# pca10059.net
KiCad netlist of a schematic drawn in Altium Designer
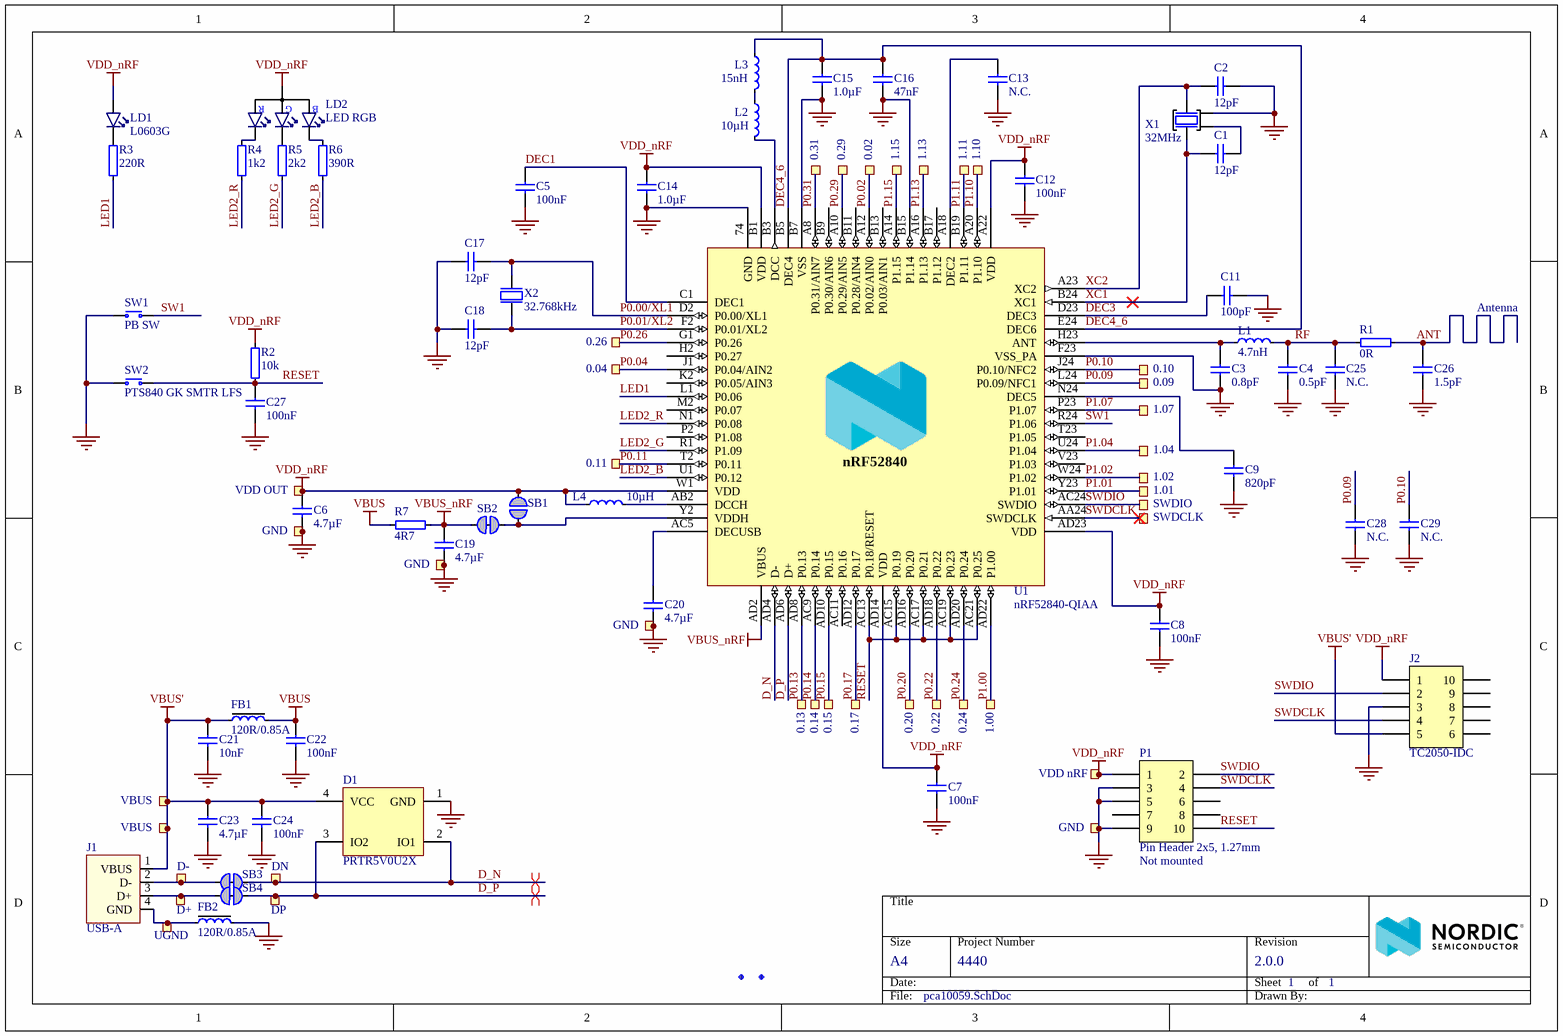
[diagram p0: pca10059.SchDoc]

(export (version "E")
  (design (tool "Eeschema 10.0.6"))
  (components
    (comp (ref "0.02")
      (value "CH")
      (footprint "Castellated_Hole_0.9mm")
      (description "Castellated Hole 0.9mm")
      (fields (field (name "PUBLISHER") "Nordic Semiconductor"))
      (libsource (lib "") (part "TESTPAD_1"))
    )
    (comp (ref "0.04")
      (value "Ø1.0mm,SMD")
      (footprint "TP_SMD_Ø1.0mm")
      (description "1.0mm circular SMD testpad")
      (fields
        (field (name "PART NUMBER") "TP_SMD_Ø1.0MM")
        (field (name "MANUFACTURER") "Nordic Semiconductor")
        (field (name "PUBLISHER") "Nordic Semiconductor")
      )
      (libsource (lib "Nordic Passive DB") (part "TESTPAD"))
    )
    (comp (ref "0.09")
      (value "CH")
      (footprint "Castellated_Hole_0.9mm")
      (description "Castellated Hole 0.9mm")
      (fields (field (name "PUBLISHER") "Nordic Semiconductor"))
      (libsource (lib "") (part "TESTPAD_3"))
    )
    (comp (ref "0.10")
      (value "CH")
      (footprint "Castellated_Hole_0.9mm")
      (description "Castellated Hole 0.9mm")
      (fields (field (name "PUBLISHER") "Nordic Semiconductor"))
      (libsource (lib "") (part "TESTPAD_3"))
    )
    (comp (ref "0.11")
      (value "Ø1.0mm,SMD")
      (footprint "TP_SMD_Ø1.0mm")
      (description "1.0mm circular SMD testpad")
      (fields
        (field (name "PART NUMBER") "TP_SMD_Ø1.0MM")
        (field (name "MANUFACTURER") "Nordic Semiconductor")
        (field (name "PUBLISHER") "Nordic Semiconductor")
      )
      (libsource (lib "Nordic Passive DB") (part "TESTPAD"))
    )
    (comp (ref "0.13")
      (value "CH")
      (footprint "Castellated_Hole_0.9mm")
      (description "Castellated Hole 0.9mm")
      (fields (field (name "PUBLISHER") "Nordic Semiconductor"))
      (libsource (lib "") (part "TESTPAD_2"))
    )
    (comp (ref "0.14")
      (value "Ø1.0mm,SMD")
      (footprint "TP_SMD_Ø1.0mm")
      (description "1.0mm circular SMD testpad")
      (fields
        (field (name "PART NUMBER") "TP_SMD_Ø1.0MM")
        (field (name "MANUFACTURER") "Nordic Semiconductor")
        (field (name "PUBLISHER") "Nordic Semiconductor")
      )
      (libsource (lib "") (part "TESTPAD_2"))
    )
    (comp (ref "0.15")
      (value "CH")
      (footprint "Castellated_Hole_0.9mm")
      (description "Castellated Hole 0.9mm")
      (fields (field (name "PUBLISHER") "Nordic Semiconductor"))
      (libsource (lib "") (part "TESTPAD_2"))
    )
    (comp (ref "0.17")
      (value "CH")
      (footprint "Castellated_Hole_0.9mm")
      (description "Castellated Hole 0.9mm")
      (fields (field (name "PUBLISHER") "Nordic Semiconductor"))
      (libsource (lib "") (part "TESTPAD_2"))
    )
    (comp (ref "0.20")
      (value "CH")
      (footprint "Castellated_Hole_0.9mm")
      (description "Castellated Hole 0.9mm")
      (fields (field (name "PUBLISHER") "Nordic Semiconductor"))
      (libsource (lib "") (part "TESTPAD_2"))
    )
    (comp (ref "0.22")
      (value "CH")
      (footprint "Castellated_Hole_0.9mm")
      (description "Castellated Hole 0.9mm")
      (fields (field (name "PUBLISHER") "Nordic Semiconductor"))
      (libsource (lib "") (part "TESTPAD_2"))
    )
    (comp (ref "0.24")
      (value "CH")
      (footprint "Castellated_Hole_0.9mm")
      (description "Castellated Hole 0.9mm")
      (fields (field (name "PUBLISHER") "Nordic Semiconductor"))
      (libsource (lib "") (part "TESTPAD_2"))
    )
    (comp (ref "0.26")
      (value "Ø1.0mm,SMD")
      (footprint "TP_SMD_Ø1.0mm")
      (description "1.0mm circular SMD testpad")
      (fields
        (field (name "PART NUMBER") "TP_SMD_Ø1.0MM")
        (field (name "MANUFACTURER") "Nordic Semiconductor")
        (field (name "PUBLISHER") "Nordic Semiconductor")
      )
      (libsource (lib "Nordic Passive DB") (part "TESTPAD"))
    )
    (comp (ref "0.29")
      (value "CH")
      (footprint "Castellated_Hole_0.9mm")
      (description "Castellated Hole 0.9mm")
      (fields (field (name "PUBLISHER") "Nordic Semiconductor"))
      (libsource (lib "") (part "TESTPAD_1"))
    )
    (comp (ref "0.31")
      (value "CH")
      (footprint "Castellated_Hole_0.9mm")
      (description "Castellated Hole 0.9mm")
      (fields (field (name "PUBLISHER") "Nordic Semiconductor"))
      (libsource (lib "") (part "TESTPAD_1"))
    )
    (comp (ref "1.00")
      (value "CH")
      (footprint "Castellated_Hole_0.9mm")
      (description "Castellated Hole 0.9mm")
      (fields (field (name "PUBLISHER") "Nordic Semiconductor"))
      (libsource (lib "") (part "TESTPAD_2"))
    )
    (comp (ref "1.01")
      (value "Ø1.0mm,SMD")
      (footprint "TP_SMD_Ø1.0mm")
      (description "1.0mm circular SMD testpad")
      (fields
        (field (name "PART NUMBER") "TP_SMD_Ø1.0MM")
        (field (name "MANUFACTURER") "Nordic Semiconductor")
        (field (name "PUBLISHER") "Nordic Semiconductor")
      )
      (libsource (lib "") (part "TESTPAD_3"))
    )
    (comp (ref "1.02")
      (value "Ø1.0mm,SMD")
      (footprint "TP_SMD_Ø1.0mm")
      (description "1.0mm circular SMD testpad")
      (fields
        (field (name "PART NUMBER") "TP_SMD_Ø1.0MM")
        (field (name "MANUFACTURER") "Nordic Semiconductor")
        (field (name "PUBLISHER") "Nordic Semiconductor")
      )
      (libsource (lib "") (part "TESTPAD_3"))
    )
    (comp (ref "1.04")
      (value "Ø1.0mm,SMD")
      (footprint "TP_SMD_Ø1.0mm")
      (description "1.0mm circular SMD testpad")
      (fields
        (field (name "PART NUMBER") "TP_SMD_Ø1.0MM")
        (field (name "MANUFACTURER") "Nordic Semiconductor")
        (field (name "PUBLISHER") "Nordic Semiconductor")
      )
      (libsource (lib "") (part "TESTPAD_3"))
    )
    (comp (ref "1.07")
      (value "Ø1.0mm,SMD")
      (footprint "TP_SMD_Ø1.0mm")
      (description "1.0mm circular SMD testpad")
      (fields
        (field (name "PART NUMBER") "TP_SMD_Ø1.0MM")
        (field (name "MANUFACTURER") "Nordic Semiconductor")
        (field (name "PUBLISHER") "Nordic Semiconductor")
      )
      (libsource (lib "") (part "TESTPAD_3"))
    )
    (comp (ref "1.10")
      (value "CH")
      (footprint "Castellated_Hole_0.9mm")
      (description "Castellated Hole 0.9mm")
      (fields (field (name "PUBLISHER") "Nordic Semiconductor"))
      (libsource (lib "") (part "TESTPAD_1"))
    )
    (comp (ref "1.11")
      (value "Ø1.0mm,SMD")
      (footprint "TP_SMD_Ø1.0mm")
      (description "1.0mm circular SMD testpad")
      (fields
        (field (name "PART NUMBER") "TP_SMD_Ø1.0MM")
        (field (name "MANUFACTURER") "Nordic Semiconductor")
        (field (name "PUBLISHER") "Nordic Semiconductor")
      )
      (libsource (lib "") (part "TESTPAD_1"))
    )
    (comp (ref "1.13")
      (value "CH")
      (footprint "Castellated_Hole_0.9mm")
      (description "Castellated Hole 0.9mm")
      (fields (field (name "PUBLISHER") "Nordic Semiconductor"))
      (libsource (lib "") (part "TESTPAD_1"))
    )
    (comp (ref "1.15")
      (value "CH")
      (footprint "Castellated_Hole_0.9mm")
      (description "Castellated Hole 0.9mm")
      (fields (field (name "PUBLISHER") "Nordic Semiconductor"))
      (libsource (lib "") (part "TESTPAD_1"))
    )
    (comp (ref "C1")
      (value "12pF")
      (footprint "CAPC0603X03L_C")
      (description "Capacitor, NP0, ±2%")
      (fields (field (name "PART NUMBER") "C0201-12p") (field (name "PUBLISHER") "Nordic Semiconductor"))
      (libsource (lib "Nordic Passive DB") (part "CAP"))
    )
    (comp (ref "C2")
      (value "12pF")
      (footprint "CAPC0603X03L_C")
      (description "Capacitor, NP0, ±2%")
      (fields (field (name "PART NUMBER") "C0201-12p") (field (name "PUBLISHER") "Nordic Semiconductor"))
      (libsource (lib "Nordic Passive DB") (part "CAP"))
    )
    (comp (ref "C3")
      (value "0.8pF")
      (footprint "CAPC0603X03L_C")
      (description "Capacitor, NP0, ±0.05pF, 50V")
      (fields
        (field (name "PART NUMBER") "C0201-0.8p")
        (field (name "MANUFACTURER") "Murata")
        (field (name "PUBLISHER") "Nordic Semiconductor")
      )
      (libsource (lib "Nordic Passive DB") (part "CAP"))
    )
    (comp (ref "C4")
      (value "0.5pF")
      (footprint "CAPC0603X03L_C")
      (description "Capacitor, NP0, ±0.05pF")
      (fields (field (name "PART NUMBER") "C0201-0.5p") (field (name "PUBLISHER") "Nordic Semiconductor"))
      (libsource (lib "Nordic Passive DB") (part "CAP"))
    )
    (comp (ref "C5")
      (value "100nF")
      (footprint "CAPC0603X03L_C")
      (description "Capacitor, X5R, ±10%")
      (fields (field (name "PART NUMBER") "C0201-100n") (field (name "PUBLISHER") "Nordic Semiconductor"))
      (libsource (lib "Nordic Passive DB") (part "CAP"))
    )
    (comp (ref "C6")
      (value "4.7µF")
      (footprint "CAPC1608X06L")
      (description "Capacitor, X5R, ±10%")
      (fields (field (name "PART NUMBER") "C0603-4µ7") (field (name "PUBLISHER") "Nordic Semiconductor"))
      (libsource (lib "Nordic Passive DB") (part "CAP"))
    )
    (comp (ref "C7")
      (value "100nF")
      (footprint "CAPC0603X03L_C")
      (description "Capacitor, X5R, ±10%")
      (fields (field (name "PART NUMBER") "C0201-100n") (field (name "PUBLISHER") "Nordic Semiconductor"))
      (libsource (lib "Nordic Passive DB") (part "CAP"))
    )
    (comp (ref "C8")
      (value "100nF")
      (footprint "CAPC0603X03L_C")
      (description "Capacitor, X5R, ±10%")
      (fields (field (name "PART NUMBER") "C0201-100n") (field (name "PUBLISHER") "Nordic Semiconductor"))
      (libsource (lib "Nordic Passive DB") (part "CAP"))
    )
    (comp (ref "C9")
      (value "820pF")
      (footprint "CAPC0603X03L_C")
      (description "Capacitor, X7R, ±10%")
      (fields (field (name "PART NUMBER") "C0201-820p") (field (name "PUBLISHER") "Nordic Semiconductor"))
      (libsource (lib "Nordic Passive DB") (part "CAP"))
    )
    (comp (ref "C11")
      (value "100pF")
      (footprint "CAPC0603X03L_C")
      (description "Capacitor, NP0, ±2%, 25V")
      (fields
        (field (name "PART NUMBER") "C0201-100p")
        (field (name "MANUFACTURER") "Murata")
        (field (name "PUBLISHER") "Nordic Semiconductor")
      )
      (libsource (lib "Nordic Passive DB") (part "CAP"))
    )
    (comp (ref "C12")
      (value "100nF")
      (footprint "CAPC0603X03L_C")
      (description "Capacitor, X5R, ±10%")
      (fields (field (name "PART NUMBER") "C0201-100n") (field (name "PUBLISHER") "Nordic Semiconductor"))
      (libsource (lib "Nordic Passive DB") (part "CAP"))
    )
    (comp (ref "C13")
      (value "N.C.")
      (footprint "CAPC0603X03L_C")
      (description "Not mounted")
      (fields (field (name "PART NUMBER") "C0201-N.C.") (field (name "PUBLISHER") "Nordic Semiconductor"))
      (libsource (lib "Nordic Passive DB") (part "CAP"))
    )
    (comp (ref "C14")
      (value "1.0µF")
      (footprint "CAPC1608X06L")
      (description "Capacitor, X7R, ±10%")
      (fields (field (name "PART NUMBER") "C0603-1µ0") (field (name "PUBLISHER") "Nordic Semiconductor"))
      (libsource (lib "Nordic Passive DB") (part "CAP"))
    )
    (comp (ref "C15")
      (value "1.0µF")
      (footprint "CAPC1608X06L")
      (description "Capacitor, X7R, ±10%")
      (fields (field (name "PART NUMBER") "C0603-1µ0") (field (name "PUBLISHER") "Nordic Semiconductor"))
      (libsource (lib "Nordic Passive DB") (part "CAP"))
    )
    (comp (ref "C16")
      (value "47nF")
      (footprint "CAPC0603X03L_C")
      (description "Capacitor, X5R, ±10%")
      (fields (field (name "PART NUMBER") "C0201-47n") (field (name "PUBLISHER") "Nordic Semiconductor"))
      (libsource (lib "Nordic Passive DB") (part "CAP"))
    )
    (comp (ref "C17")
      (value "12pF")
      (footprint "CAPC0603X03L_C")
      (description "Capacitor, NP0, ±2%")
      (fields (field (name "PART NUMBER") "C0201-12p") (field (name "PUBLISHER") "Nordic Semiconductor"))
      (libsource (lib "Nordic Passive DB") (part "CAP"))
    )
    (comp (ref "C18")
      (value "12pF")
      (footprint "CAPC0603X03L_C")
      (description "Capacitor, NP0, ±2%")
      (fields (field (name "PART NUMBER") "C0201-12p") (field (name "PUBLISHER") "Nordic Semiconductor"))
      (libsource (lib "Nordic Passive DB") (part "CAP"))
    )
    (comp (ref "C19")
      (value "4.7µF")
      (footprint "CAPC1005X04L")
      (description "Capacitor, X5R, ±20%")
      (fields (field (name "PART NUMBER") "C0402-4µ7") (field (name "PUBLISHER") "Nordic Semiconductor"))
      (libsource (lib "Nordic Passive DB") (part "CAP"))
    )
    (comp (ref "C20")
      (value "4.7µF")
      (footprint "CAPC1608X06L")
      (description "Capacitor, X5R, ±10%")
      (fields (field (name "PART NUMBER") "C0603-4µ7") (field (name "PUBLISHER") "Nordic Semiconductor"))
      (libsource (lib "Nordic Passive DB") (part "CAP"))
    )
    (comp (ref "C21")
      (value "10nF")
      (footprint "CAPC0603X03L_C")
      (description "Capacitor, X7R, ±10%")
      (fields (field (name "PART NUMBER") "C0201-10n") (field (name "PUBLISHER") "Nordic Semiconductor"))
      (libsource (lib "Nordic Passive DB") (part "CAP"))
    )
    (comp (ref "C22")
      (value "100nF")
      (footprint "CAPC0603X03L_C")
      (description "Capacitor, X5R, ±10%")
      (fields (field (name "PART NUMBER") "C0201-100n") (field (name "PUBLISHER") "Nordic Semiconductor"))
      (libsource (lib "Nordic Passive DB") (part "CAP"))
    )
    (comp (ref "C23")
      (value "4.7µF")
      (footprint "CAPC1005X04L")
      (description "Capacitor, X5R, ±20%")
      (fields (field (name "PART NUMBER") "C0402-4µ7") (field (name "PUBLISHER") "Nordic Semiconductor"))
      (libsource (lib "Nordic Passive DB") (part "CAP"))
    )
    (comp (ref "C24")
      (value "100nF")
      (footprint "CAPC0603X03L_C")
      (description "Capacitor, X5R, ±10%")
      (fields (field (name "PART NUMBER") "C0201-100n") (field (name "PUBLISHER") "Nordic Semiconductor"))
      (libsource (lib "Nordic Passive DB") (part "CAP"))
    )
    (comp (ref "C25")
      (value "N.C.")
      (footprint "CAPC0603X03L_C")
      (description "Not mounted")
      (fields (field (name "PART NUMBER") "C0201-N.C.") (field (name "PUBLISHER") "Nordic Semiconductor"))
      (libsource (lib "Nordic Passive DB") (part "CAP"))
    )
    (comp (ref "C26")
      (value "1.5pF")
      (footprint "CAPC0603X03L_C")
      (description "Capacitor, NP0, ±0.1pF")
      (fields (field (name "PART NUMBER") "C0201-1.5p") (field (name "PUBLISHER") "Nordic Semiconductor"))
      (libsource (lib "Nordic Passive DB") (part "CAP"))
    )
    (comp (ref "C27")
      (value "100nF")
      (footprint "CAPC0603X03L_C")
      (description "Capacitor, X5R, ±10%")
      (fields (field (name "PART NUMBER") "C0201-100n") (field (name "PUBLISHER") "Nordic Semiconductor"))
      (libsource (lib "Nordic Passive DB") (part "CAP"))
    )
    (comp (ref "C28")
      (value "N.C.")
      (footprint "CAPC1005X04L")
      (description "Not mounted")
      (fields (field (name "PART NUMBER") "C0402-N.C.") (field (name "PUBLISHER") "Nordic Semiconductor"))
      (libsource (lib "Nordic Passive DB") (part "CAP"))
    )
    (comp (ref "C29")
      (value "N.C.")
      (footprint "CAPC1005X04L")
      (description "Not mounted")
      (fields (field (name "PART NUMBER") "C0402-N.C.") (field (name "PUBLISHER") "Nordic Semiconductor"))
      (libsource (lib "Nordic Passive DB") (part "CAP"))
    )
    (comp (ref "D+")
      (value "Ø1.0mm,SMD")
      (footprint "TP_SMD_Ø1.0mm")
      (description "1.0mm circular SMD testpad")
      (fields
        (field (name "PART NUMBER") "TP_SMD_Ø1.0MM")
        (field (name "MANUFACTURER") "Nordic Semiconductor")
        (field (name "PUBLISHER") "Nordic Semiconductor")
      )
      (libsource (lib "") (part "TESTPAD_2"))
    )
    (comp (ref "D-")
      (value "Ø1.0mm,SMD")
      (footprint "TP_SMD_Ø1.0mm")
      (description "1.0mm circular SMD testpad")
      (fields
        (field (name "PART NUMBER") "TP_SMD_Ø1.0MM")
        (field (name "MANUFACTURER") "Nordic Semiconductor")
        (field (name "PUBLISHER") "Nordic Semiconductor")
      )
      (libsource (lib "") (part "TESTPAD_1"))
    )
    (comp (ref "D1")
      (value "PRTR5V0U2X")
      (footprint "SOT190P230X110-4L")
      (description "Ultra low capacitance double rail-to-rail ESD protection diode")
      (fields (field (name "MANUFACTURER") "NXP") (field (name "PUBLISHER") "Nordic Semiconductor"))
      (libsource (lib "Nordic Discrete DB") (part "PRTR5V0U2X"))
    )
    (comp (ref "DN")
      (value "Ø1.0mm,SMD")
      (footprint "TP_SMD_Ø1.0mm")
      (description "1.0mm circular SMD testpad")
      (fields
        (field (name "PART NUMBER") "TP_SMD_Ø1.0MM")
        (field (name "MANUFACTURER") "Nordic Semiconductor")
        (field (name "PUBLISHER") "Nordic Semiconductor")
      )
      (libsource (lib "") (part "TESTPAD_1"))
    )
    (comp (ref "DP")
      (value "Ø1.0mm,SMD")
      (footprint "TP_SMD_Ø1.0mm")
      (description "1.0mm circular SMD testpad")
      (fields
        (field (name "PART NUMBER") "TP_SMD_Ø1.0MM")
        (field (name "MANUFACTURER") "Nordic Semiconductor")
        (field (name "PUBLISHER") "Nordic Semiconductor")
      )
      (libsource (lib "") (part "TESTPAD_2"))
    )
    (comp (ref "FB1")
      (value "120R/0.85A")
      (footprint "INDC0603X03L_C")
      (description "Ferrite Bead, 120 Ohm @ 100MHz, 850mA, 150 mOhm Max")
      (fields
        (field (name "PART NUMBER") "FB0201-120R@100M-850mA")
        (field (name "MANUFACTURER") "Taiyo Yuden")
        (field (name "PUBLISHER") "Nordic Semiconductor")
      )
      (libsource (lib "Nordic Passive DB") (part "IND_F"))
    )
    (comp (ref "FB2")
      (value "120R/0.85A")
      (footprint "INDC0603X03L_C")
      (description "Ferrite Bead, 120 Ohm @ 100MHz, 850mA, 150 mOhm Max")
      (fields
        (field (name "PART NUMBER") "FB0201-120R@100M-850mA")
        (field (name "MANUFACTURER") "Taiyo Yuden")
        (field (name "PUBLISHER") "Nordic Semiconductor")
      )
      (libsource (lib "Nordic Passive DB") (part "IND_F"))
    )
    (comp (ref "Fid1")
      (value "Fiducial mark")
      (footprint "Fiducial_Square")
      (description "Fiducial Mark")
      (fields
        (field (name "PART NUMBER") "Fid-Mark-Square")
        (field (name "PUBLISHER") "Nordic Semiconductor")
      )
      (libsource (lib "Nordic Passive DB") (part "Fiducial"))
    )
    (comp (ref "Fid2")
      (value "Fiducial mark")
      (footprint "Fiducial")
      (description "Fiducial Mark")
      (fields (field (name "PART NUMBER") "Fid-Mark") (field (name "PUBLISHER") "Nordic Semiconductor"))
      (libsource (lib "Nordic Passive DB") (part "Fiducial"))
    )
    (comp (ref "GND1")
      (value "GND")
      (footprint "Castellated_Hole_0.9mm")
      (description "Castellated Hole 0.9mm")
      (fields (field (name "PUBLISHER") "Nordic Semiconductor"))
      (libsource (lib "Nordic Passive DB") (part "TESTPAD"))
    )
    (comp (ref "GND2")
      (value "GND")
      (footprint "Castellated_Hole_0.9mm_S")
      (description "Castellated Hole 0.9mm")
      (fields
        (field (name "PART NUMBER") "Castellated Hole 0.9mm_S")
        (field (name "PUBLISHER") "Nordic Semiconductor")
      )
      (libsource (lib "Nordic Passive DB") (part "TESTPAD"))
    )
    (comp (ref "GND3")
      (value "GND")
      (footprint "Castellated_Hole_0.9mm_S")
      (description "Castellated Hole 0.9mm")
      (fields
        (field (name "PART NUMBER") "Castellated Hole 0.9mm_S")
        (field (name "PUBLISHER") "Nordic Semiconductor")
      )
      (libsource (lib "Nordic Passive DB") (part "TESTPAD"))
    )
    (comp (ref "GND4")
      (value "GND")
      (footprint "TP_SMD_Ø1.0mm")
      (description "1.0mm circular SMD testpad")
      (fields
        (field (name "PART NUMBER") "TP_SMD_Ø1.0MM")
        (field (name "MANUFACTURER") "Nordic Semiconductor")
        (field (name "PUBLISHER") "Nordic Semiconductor")
      )
      (libsource (lib "Nordic Passive DB") (part "TESTPAD"))
    )
    (comp (ref "J1")
      (value "USB-A")
      (footprint "USB-A-PCB")
      (description "USB-A PCB footprint")
      (fields (field (name "PART NUMBER") "USB-A-PCB") (field (name "PUBLISHER") "Nordic Semiconductor"))
      (libsource (lib "Nordic Passive DB") (part "USB-PCB-A"))
    )
    (comp (ref "J2")
      (value "TC2050-IDC")
      (footprint "TC2050-IDC-NLFP")
      (description "CBL PLUG-OF-NAILS 10-PIN")
      (fields
        (field (name "PART NUMBER") "TC2050-IDC-NLFP")
        (field (name "MANUFACTURER") "Tag-Connect LLC")
        (field (name "PUBLISHER") "Nordic Semiconductor")
      )
      (libsource (lib "Nordic Passive DB") (part "CONN-2x5_var2_No_BOM"))
    )
    (comp (ref "L1")
      (value "4.7nH")
      (footprint "INDC0603X03L_C")
      (description "Inductor, 350mA, ±3%")
      (fields
        (field (name "PART NUMBER") "L0201-4n7")
        (field (name "MANUFACTURER") "Murata")
        (field (name "PUBLISHER") "Nordic Semiconductor")
      )
      (libsource (lib "Nordic Passive DB") (part "IND"))
    )
    (comp (ref "L2")
      (value "10µH")
      (footprint "INDC1608X06L")
      (description "Inductor, 80mA, ±10%")
      (fields
        (field (name "PART NUMBER") "L0603-10µ")
        (field (name "MANUFACTURER") "Taiyo Yuden")
        (field (name "PUBLISHER") "Nordic Semiconductor")
      )
      (libsource (lib "Nordic Passive DB") (part "IND"))
    )
    (comp (ref "L3")
      (value "15nH")
      (footprint "INDC1005X04L")
      (description "Inductor, 320mA, ±5%")
      (fields
        (field (name "PART NUMBER") "L0402-15n")
        (field (name "MANUFACTURER") "Taiyo Yuden")
        (field (name "PUBLISHER") "Nordic Semiconductor")
      )
      (libsource (lib "Nordic Passive DB") (part "IND"))
    )
    (comp (ref "L4")
      (value "10µH")
      (footprint "INDC1608X06L")
      (description "Inductor, 80mA, ±10%")
      (fields
        (field (name "PART NUMBER") "L0603-10µ")
        (field (name "MANUFACTURER") "Taiyo Yuden")
        (field (name "PUBLISHER") "Nordic Semiconductor")
      )
      (libsource (lib "Nordic Passive DB") (part "IND"))
    )
    (comp (ref "LD1")
      (value "L0603G")
      (footprint "LED_0603_G")
      (description "LED, Green, 0603, 573nm, Vf=2.0V, 24mcd, - 40 to +85°C")
      (fields
        (field (name "PART NUMBER") "VS 25C7M5")
        (field (name "MANUFACTURER") "Victory Electronics")
        (field (name "PUBLISHER") "Nordic Semiconductor")
      )
      (libsource (lib "Nordic Discrete DB") (part "D{colon}LED"))
    )
    (comp (ref "LD2")
      (value "LED RGB")
      (footprint "LED_RGB_0603")
      (description "RGB LED 1.60 mm x 0.80 mm SMD")
      (fields
        (field (name "PART NUMBER") "APHF1608LSEEQBDZGKC")
        (field (name "MANUFACTURER") "Kingbright Company LLC")
        (field (name "PUBLISHER") "Nordic Semiconductor")
      )
      (libsource (lib "Nordic Discrete DB") (part "D{colon}LED_RGB"))
    )
    (comp (ref "P1")
      (value "Pin Header 2x5, 1.27mm")
      (footprint "HDR_2x5-SMD-1.27mm-NC")
      (description "Pin Header 2x5, 1.27mm (50mil), SMD, Keying Shroud")
      (fields
        (field (name "PART NUMBER") "Pin Header 2x5 SMD, 1.27mm, KS, N.C.")
        (field (name "ASSEMBLY") "Not mounted")
        (field (name "MANUFACTURER") "W-CON")
        (field (name "PUBLISHER") "Nordic Semiconductor")
      )
      (libsource (lib "Nordic Passive DB") (part "CONN-2x5"))
    )
    (comp (ref "R1")
      (value "0R")
      (footprint "RESC0603X03L_C")
      (description "Resistor, ±5%, 0.05W")
      (fields (field (name "PART NUMBER") "R0201-0R") (field (name "PUBLISHER") "Nordic Semiconductor"))
      (libsource (lib "Nordic Passive DB") (part "RES_1"))
    )
    (comp (ref "R2")
      (value "10k")
      (footprint "RESC0603X03L_C")
      (description "Resistor, ±1%, 0.05W")
      (fields (field (name "PART NUMBER") "R0201-10k") (field (name "PUBLISHER") "Nordic Semiconductor"))
      (libsource (lib "Nordic Passive DB") (part "RES_1"))
    )
    (comp (ref "R3")
      (value "220R")
      (footprint "RESC0603X03L_C")
      (description "Resistor, ±1%, 0.05W")
      (fields (field (name "PART NUMBER") "R0201-220") (field (name "PUBLISHER") "Nordic Semiconductor"))
      (libsource (lib "Nordic Passive DB") (part "RES_1"))
    )
    (comp (ref "R4")
      (value "1k2")
      (footprint "RESC0603X03L_C")
      (description "Resistor, ±1%, 0.05W")
      (fields (field (name "PART NUMBER") "R0201-1k2") (field (name "PUBLISHER") "Nordic Semiconductor"))
      (libsource (lib "Nordic Passive DB") (part "RES_1"))
    )
    (comp (ref "R5")
      (value "2k2")
      (footprint "RESC0603X03L_C")
      (description "Resistor, ±1%, 0.05W")
      (fields (field (name "PART NUMBER") "R0201-2k2") (field (name "PUBLISHER") "Nordic Semiconductor"))
      (libsource (lib "Nordic Passive DB") (part "RES_1"))
    )
    (comp (ref "R6")
      (value "390R")
      (footprint "RESC0603X03L_C")
      (description "Resistor, ±1%, 0.05W")
      (fields (field (name "PART NUMBER") "R0201-390") (field (name "PUBLISHER") "Nordic Semiconductor"))
      (libsource (lib "Nordic Passive DB") (part "RES_1"))
    )
    (comp (ref "R7")
      (value "4R7")
      (footprint "RESC0603X03L_C")
      (description "Resistor, ±1%, 0.05W")
      (fields (field (name "PART NUMBER") "R0201-4R7") (field (name "PUBLISHER") "Nordic Semiconductor"))
      (libsource (lib "Nordic Passive DB") (part "RES_1"))
    )
    (comp (ref "SB1")
      (value "Solderbridge")
      (footprint "Solderbridge")
      (fields (field (name "PUBLISHER") "Nordic Semiconductor"))
      (libsource (lib "Nordic Passive DB") (part "SOLDERBRIDGE"))
    )
    (comp (ref "SB2")
      (value "Solderbridge")
      (footprint "Solderbridge_Shorted")
      (description "Shorted Solderbridge")
      (fields
        (field (name "PART NUMBER") "Solderbridge Shorted")
        (field (name "PUBLISHER") "Nordic Semiconductor")
      )
      (libsource (lib "Nordic Passive DB") (part "SOLDERBRIDGE_SHORTED"))
    )
    (comp (ref "SB3")
      (value "Solderbridge")
      (footprint "Solderbridge_Shorted")
      (description "Shorted Solderbridge")
      (fields
        (field (name "PART NUMBER") "Solderbridge Shorted")
        (field (name "PUBLISHER") "Nordic Semiconductor")
      )
      (libsource (lib "Nordic Passive DB") (part "SOLDERBRIDGE_SHORTED"))
    )
    (comp (ref "SB4")
      (value "Solderbridge")
      (footprint "Solderbridge_Shorted")
      (description "Shorted Solderbridge")
      (fields
        (field (name "PART NUMBER") "Solderbridge Shorted")
        (field (name "PUBLISHER") "Nordic Semiconductor")
      )
      (libsource (lib "Nordic Passive DB") (part "SOLDERBRIDGE_SHORTED"))
    )
    (comp (ref "SW1")
      (value "PB SW")
      (footprint "C&K_PTS810")
      (description "Tactile Switch, SPNO, SMD, 260gf, 4.2x3.2x2.5mm")
      (fields
        (field (name "PART NUMBER") "PTS810 SJK 250 SMTR LFS")
        (field (name "MANUFACTURER") "C&K Components")
        (field (name "PUBLISHER") "Nordic Semiconductor")
      )
      (libsource (lib "Nordic Discrete DB") (part "SW-PB"))
    )
    (comp (ref "SW2")
      (value "PTS840 GK SMTR LFS")
      (footprint "EVQP7A/J/B/K")
      (description "Microminiature SMT Switch, Side Actuated")
      (fields
        (field (name "MANUFACTURER") "C&K Components")
        (field (name "PUBLISHER") "Nordic Semiconductor")
      )
      (libsource (lib "Nordic Discrete DB") (part "SW-PB"))
    )
    (comp (ref "SWDCLK")
      (value "CH")
      (footprint "Castellated_Hole_0.9mm_D")
      (description "Castellated Hole 0.9mm")
      (fields
        (field (name "PART NUMBER") "Castellated Hole 0.9mm_D")
        (field (name "PUBLISHER") "Nordic Semiconductor")
      )
      (libsource (lib "") (part "TESTPAD_3"))
    )
    (comp (ref "SWDIO")
      (value "CH")
      (footprint "Castellated_Hole_0.9mm_D")
      (description "Castellated Hole 0.9mm")
      (fields
        (field (name "PART NUMBER") "Castellated Hole 0.9mm_D")
        (field (name "PUBLISHER") "Nordic Semiconductor")
      )
      (libsource (lib "") (part "TESTPAD_3"))
    )
    (comp (ref "U1")
      (value "nRF52840-QIAA")
      (footprint "AQFN50P700X700X85_HS-74N")
      (description "Multi-protocol Bluetooth Low Energy, IEEE 802.15.4, ANT and 2.4GHz proprietary system-on-chip")
      (fields
        (field (name "PART NUMBER") "nRF52840-QIAAD0")
        (field (name "MANUFACTURER") "Nordic Semiconductor")
        (field (name "PUBLISHER") "Nordic Semiconductor")
      )
      (libsource (lib "Nordic Active DB") (part "nRF52840_QIAA"))
    )
    (comp (ref "UGND")
      (value "Ø1.0mm,SMD")
      (footprint "TP_SMD_Ø1.0mm")
      (description "1.0mm circular SMD testpad")
      (fields
        (field (name "PART NUMBER") "TP_SMD_Ø1.0MM")
        (field (name "MANUFACTURER") "Nordic Semiconductor")
        (field (name "PUBLISHER") "Nordic Semiconductor")
      )
      (libsource (lib "") (part "TESTPAD_2"))
    )
    (comp (ref "VBUS1")
      (value "VBUS")
      (footprint "Castellated_Hole_0.9mm")
      (description "Castellated Hole 0.9mm")
      (fields (field (name "PUBLISHER") "Nordic Semiconductor"))
      (libsource (lib "Nordic Passive DB") (part "TESTPAD"))
    )
    (comp (ref "VBUS2")
      (value "VBUS")
      (footprint "TP_SMD_Ø1.0mm")
      (description "1.0mm circular SMD testpad")
      (fields
        (field (name "PART NUMBER") "TP_SMD_Ø1.0MM")
        (field (name "MANUFACTURER") "Nordic Semiconductor")
        (field (name "PUBLISHER") "Nordic Semiconductor")
      )
      (libsource (lib "Nordic Passive DB") (part "TESTPAD"))
    )
    (comp (ref "VDD nRF")
      (value "Ø1.0mm,SMD")
      (footprint "TP_SMD_Ø1.0mm")
      (description "1.0mm circular SMD testpad")
      (fields
        (field (name "PART NUMBER") "TP_SMD_Ø1.0MM")
        (field (name "MANUFACTURER") "Nordic Semiconductor")
        (field (name "PUBLISHER") "Nordic Semiconductor")
      )
      (libsource (lib "Nordic Passive DB") (part "TESTPAD"))
    )
    (comp (ref "VDD OUT")
      (value "CH")
      (footprint "Castellated_Hole_0.9mm")
      (description "Castellated Hole 0.9mm")
      (fields (field (name "PUBLISHER") "Nordic Semiconductor"))
      (libsource (lib "Nordic Passive DB") (part "TESTPAD"))
    )
    (comp (ref "X1")
      (value "32MHz")
      (footprint "BT-XTAL_2016")
      (description "XTAL SMD 2016, 32MHz, Cl=8pF, Tol: ±10ppm, Stab: ±10ppm")
      (fields
        (field (name "PART NUMBER") "XTAL_SMD2016_32MHz_8pF_Murata")
        (field (name "MANUFACTURER") "Murata")
        (field (name "PUBLISHER") "Nordic Semiconductor")
      )
      (libsource (lib "Nordic Discrete DB") (part "XTAL_4-pin"))
    )
    (comp (ref "X2")
      (value "32.768kHz")
      (footprint "XTAL_2012")
      (description "XTAL SMD 2012, 32.768kHz, 9pF, ±20ppm")
      (fields
        (field (name "PART NUMBER") "XTAL_SMD2012_32.768kHz_9pF_Seiko")
        (field (name "MANUFACTURER") "Seiko")
        (field (name "PUBLISHER") "Nordic Semiconductor")
      )
      (libsource (lib "Nordic Discrete DB") (part "XTAL_2-pin"))
    )
  )
  (nets
    (net (code "1") (name "/ANT") (class "Default")
      (node (ref "C26") (pin "2") (pinfunction "2_2") (pintype "passive"))
      (node (ref "R1") (pin "2") (pinfunction "2_2") (pintype "passive"))
    )
    (net (code "2") (name "/DEC1") (class "Default")
      (node (ref "C5") (pin "1") (pinfunction "1_1") (pintype "passive"))
      (node (ref "U1") (pin "C1") (pinfunction "DEC1_C1") (pintype "power_in"))
    )
    (net (code "3") (name "/DEC3") (class "Default")
      (node (ref "C11") (pin "1") (pinfunction "1_1") (pintype "passive"))
      (node (ref "U1") (pin "D23") (pinfunction "DEC3_D23") (pintype "power_in"))
    )
    (net (code "4") (name "/DEC4_6") (class "Default")
      (node (ref "C15") (pin "2") (pinfunction "2_2") (pintype "passive"))
      (node (ref "C16") (pin "1") (pinfunction "1_1") (pintype "passive"))
      (node (ref "L3") (pin "1") (pinfunction "1_1") (pintype "passive"))
      (node (ref "U1") (pin "B5") (pinfunction "DEC4_B5") (pintype "power_in"))
      (node (ref "U1") (pin "E24") (pinfunction "DEC6_E24") (pintype "power_in"))
    )
    (net (code "5") (name "/D_N") (class "Default")
      (node (ref "D1") (pin "2") (pinfunction "IO1_2") (pintype "passive"))
      (node (ref "DN") (pin "1") (pinfunction "1_1") (pintype "passive"))
      (node (ref "SB3") (pin "1") (pinfunction "0_1") (pintype "passive"))
      (node (ref "U1") (pin "AD4") (pinfunction "D-_AD4") (pintype "bidirectional"))
    )
    (net (code "6") (name "/D_P") (class "Default")
      (node (ref "D1") (pin "3") (pinfunction "IO2_3") (pintype "passive"))
      (node (ref "DP") (pin "1") (pinfunction "1_1") (pintype "passive"))
      (node (ref "SB4") (pin "1") (pinfunction "0_1") (pintype "passive"))
      (node (ref "U1") (pin "AD6") (pinfunction "D+_AD6") (pintype "bidirectional"))
    )
    (net (code "7") (name "/LED1") (class "Default")
      (node (ref "R3") (pin "1") (pinfunction "1_1") (pintype "passive"))
      (node (ref "U1") (pin "L1") (pinfunction "P0.06_L1") (pintype "bidirectional"))
    )
    (net (code "8") (name "/LED2_B") (class "Default")
      (node (ref "R6") (pin "1") (pinfunction "1_1") (pintype "passive"))
      (node (ref "U1") (pin "U1") (pinfunction "P0.12_U1") (pintype "bidirectional"))
    )
    (net (code "9") (name "/LED2_G") (class "Default")
      (node (ref "R5") (pin "1") (pinfunction "1_1") (pintype "passive"))
      (node (ref "U1") (pin "R1") (pinfunction "P1.09_R1") (pintype "bidirectional"))
    )
    (net (code "10") (name "/LED2_R") (class "Default")
      (node (ref "R4") (pin "1") (pinfunction "1_1") (pintype "passive"))
      (node (ref "U1") (pin "N1") (pinfunction "P0.08_N1") (pintype "bidirectional"))
    )
    (net (code "11") (name "/P0.00{slash}XL1") (class "Default")
      (node (ref "C17") (pin "1") (pinfunction "1_1") (pintype "passive"))
      (node (ref "U1") (pin "D2") (pinfunction "P0.00/XL1_D2") (pintype "bidirectional"))
      (node (ref "X2") (pin "1") (pinfunction "inp_1") (pintype "passive"))
    )
    (net (code "12") (name "/P0.01{slash}XL2") (class "Default")
      (node (ref "C18") (pin "1") (pinfunction "1_1") (pintype "passive"))
      (node (ref "U1") (pin "F2") (pinfunction "P0.01/XL2_F2") (pintype "bidirectional"))
      (node (ref "X2") (pin "2") (pinfunction "out_2") (pintype "passive"))
    )
    (net (code "13") (name "/P0.02") (class "Default")
      (node (ref "0.02") (pin "1") (pinfunction "1_1") (pintype "passive"))
      (node (ref "U1") (pin "A12") (pinfunction "P0.02/AIN0_A12") (pintype "bidirectional"))
    )
    (net (code "14") (name "/P0.04") (class "Default")
      (node (ref "0.04") (pin "1") (pinfunction "1_1") (pintype "passive"))
      (node (ref "U1") (pin "J1") (pinfunction "P0.04/AIN2_J1") (pintype "bidirectional"))
    )
    (net (code "15") (name "/P0.09") (class "Default")
      (node (ref "0.09") (pin "1") (pinfunction "1_1") (pintype "passive"))
      (node (ref "C28") (pin "2") (pinfunction "2_2") (pintype "passive"))
      (node (ref "U1") (pin "L24") (pinfunction "P0.09/NFC1_L24") (pintype "bidirectional"))
    )
    (net (code "16") (name "/P0.10") (class "Default")
      (node (ref "0.10") (pin "1") (pinfunction "1_1") (pintype "passive"))
      (node (ref "C29") (pin "1") (pinfunction "1_1") (pintype "passive"))
      (node (ref "U1") (pin "J24") (pinfunction "P0.10/NFC2_J24") (pintype "bidirectional"))
    )
    (net (code "17") (name "/P0.11") (class "Default")
      (node (ref "0.11") (pin "1") (pinfunction "1_1") (pintype "passive"))
      (node (ref "U1") (pin "T2") (pinfunction "P0.11_T2") (pintype "bidirectional"))
    )
    (net (code "18") (name "/P0.13") (class "Default")
      (node (ref "0.13") (pin "1") (pinfunction "1_1") (pintype "passive"))
      (node (ref "U1") (pin "AD8") (pinfunction "P0.13_AD8") (pintype "bidirectional"))
    )
    (net (code "19") (name "/P0.14") (class "Default")
      (node (ref "0.14") (pin "1") (pinfunction "1_1") (pintype "passive"))
      (node (ref "U1") (pin "AC9") (pinfunction "P0.14_AC9") (pintype "bidirectional"))
    )
    (net (code "20") (name "/P0.15") (class "Default")
      (node (ref "0.15") (pin "1") (pinfunction "1_1") (pintype "passive"))
      (node (ref "U1") (pin "AD10") (pinfunction "P0.15_AD10") (pintype "bidirectional"))
    )
    (net (code "21") (name "/P0.17") (class "Default")
      (node (ref "0.17") (pin "1") (pinfunction "1_1") (pintype "passive"))
      (node (ref "U1") (pin "AD12") (pinfunction "P0.17_AD12") (pintype "bidirectional"))
    )
    (net (code "22") (name "/P0.20") (class "Default")
      (node (ref "0.20") (pin "1") (pinfunction "1_1") (pintype "passive"))
      (node (ref "U1") (pin "AD16") (pinfunction "P0.20_AD16") (pintype "bidirectional"))
    )
    (net (code "23") (name "/P0.22") (class "Default")
      (node (ref "0.22") (pin "1") (pinfunction "1_1") (pintype "passive"))
      (node (ref "U1") (pin "AD18") (pinfunction "P0.22_AD18") (pintype "bidirectional"))
    )
    (net (code "24") (name "/P0.24") (class "Default")
      (node (ref "0.24") (pin "1") (pinfunction "1_1") (pintype "passive"))
      (node (ref "U1") (pin "AD20") (pinfunction "P0.24_AD20") (pintype "bidirectional"))
    )
    (net (code "25") (name "/P0.26") (class "Default")
      (node (ref "0.26") (pin "1") (pinfunction "1_1") (pintype "passive"))
      (node (ref "U1") (pin "G1") (pinfunction "P0.26_G1") (pintype "bidirectional"))
    )
    (net (code "26") (name "/P0.29") (class "Default")
      (node (ref "0.29") (pin "1") (pinfunction "1_1") (pintype "passive"))
      (node (ref "U1") (pin "A10") (pinfunction "P0.29/AIN5_A10") (pintype "bidirectional"))
    )
    (net (code "27") (name "/P0.31") (class "Default")
      (node (ref "0.31") (pin "1") (pinfunction "1_1") (pintype "passive"))
      (node (ref "U1") (pin "A8") (pinfunction "P0.31/AIN7_A8") (pintype "bidirectional"))
    )
    (net (code "28") (name "/P1.00") (class "Default")
      (node (ref "1.00") (pin "1") (pinfunction "1_1") (pintype "passive"))
      (node (ref "U1") (pin "AD22") (pinfunction "P1.00_AD22") (pintype "bidirectional"))
    )
    (net (code "29") (name "/P1.01") (class "Default")
      (node (ref "1.01") (pin "1") (pinfunction "1_1") (pintype "passive"))
      (node (ref "U1") (pin "Y23") (pinfunction "P1.01_Y23") (pintype "bidirectional"))
    )
    (net (code "30") (name "/P1.02") (class "Default")
      (node (ref "1.02") (pin "1") (pinfunction "1_1") (pintype "passive"))
      (node (ref "U1") (pin "W24") (pinfunction "P1.02_W24") (pintype "bidirectional"))
    )
    (net (code "31") (name "/P1.04") (class "Default")
      (node (ref "1.04") (pin "1") (pinfunction "1_1") (pintype "passive"))
      (node (ref "U1") (pin "U24") (pinfunction "P1.04_U24") (pintype "bidirectional"))
    )
    (net (code "32") (name "/P1.07") (class "Default")
      (node (ref "1.07") (pin "1") (pinfunction "1_1") (pintype "passive"))
      (node (ref "U1") (pin "P23") (pinfunction "P1.07_P23") (pintype "bidirectional"))
    )
    (net (code "33") (name "/P1.10") (class "Default")
      (node (ref "1.10") (pin "1") (pinfunction "1_1") (pintype "passive"))
      (node (ref "U1") (pin "A20") (pinfunction "P1.10_A20") (pintype "bidirectional"))
    )
    (net (code "34") (name "/P1.11") (class "Default")
      (node (ref "1.11") (pin "1") (pinfunction "1_1") (pintype "passive"))
      (node (ref "U1") (pin "B19") (pinfunction "P1.11_B19") (pintype "bidirectional"))
    )
    (net (code "35") (name "/P1.13") (class "Default")
      (node (ref "1.13") (pin "1") (pinfunction "1_1") (pintype "passive"))
      (node (ref "U1") (pin "A16") (pinfunction "P1.13_A16") (pintype "bidirectional"))
    )
    (net (code "36") (name "/P1.15") (class "Default")
      (node (ref "1.15") (pin "1") (pinfunction "1_1") (pintype "passive"))
      (node (ref "U1") (pin "A14") (pinfunction "P1.15_A14") (pintype "bidirectional"))
    )
    (net (code "37") (name "/RESET") (class "Default")
      (node (ref "C27") (pin "2") (pinfunction "2_2") (pintype "passive"))
      (node (ref "P1") (pin "10") (pinfunction "10_10") (pintype "passive"))
      (node (ref "R2") (pin "1") (pinfunction "1_1") (pintype "passive"))
      (node (ref "SW2") (pin "1") (pinfunction "N.O_1") (pintype "passive"))
      (node (ref "U1") (pin "AC13") (pinfunction "P0.18/RESET_AC13") (pintype "bidirectional"))
      (node (ref "U1") (pin "AC15") (pinfunction "P0.19_AC15") (pintype "bidirectional"))
      (node (ref "U1") (pin "AC17") (pinfunction "P0.21_AC17") (pintype "bidirectional"))
      (node (ref "U1") (pin "AC19") (pinfunction "P0.23_AC19") (pintype "bidirectional"))
      (node (ref "U1") (pin "AC21") (pinfunction "P0.25_AC21") (pintype "bidirectional"))
    )
    (net (code "38") (name "/RF") (class "Default")
      (node (ref "C25") (pin "1") (pinfunction "1_1") (pintype "passive"))
      (node (ref "C4") (pin "2") (pinfunction "2_2") (pintype "passive"))
      (node (ref "L1") (pin "2") (pinfunction "2_2") (pintype "passive"))
      (node (ref "R1") (pin "1") (pinfunction "1_1") (pintype "passive"))
    )
    (net (code "39") (name "/SW1") (class "Default")
      (node (ref "SW1") (pin "1") (pinfunction "N.O_1") (pintype "passive"))
      (node (ref "U1") (pin "R24") (pinfunction "P1.06_R24") (pintype "bidirectional"))
    )
    (net (code "40") (name "/SWDCLK") (class "Default")
      (node (ref "J2") (pin "4") (pinfunction "4_4") (pintype "passive"))
      (node (ref "P1") (pin "4") (pinfunction "4_4") (pintype "passive"))
      (node (ref "SWDCLK") (pin "1") (pinfunction "1_1") (pintype "passive"))
      (node (ref "U1") (pin "AA24") (pinfunction "SWDCLK_AA24") (pintype "input"))
    )
    (net (code "41") (name "/SWDIO") (class "Default")
      (node (ref "J2") (pin "2") (pinfunction "2_2") (pintype "passive"))
      (node (ref "P1") (pin "2") (pinfunction "2_2") (pintype "passive"))
      (node (ref "SWDIO") (pin "1") (pinfunction "1_1") (pintype "passive"))
      (node (ref "U1") (pin "AC24") (pinfunction "SWDIO_AC24") (pintype "bidirectional"))
    )
    (net (code "42") (name "/XC1") (class "Default")
      (node (ref "C1") (pin "1") (pinfunction "1_1") (pintype "passive"))
      (node (ref "U1") (pin "B24") (pinfunction "XC1_B24") (pintype "input"))
      (node (ref "X1") (pin "1") (pinfunction "IN_1") (pintype "passive"))
    )
    (net (code "43") (name "/XC2") (class "Default")
      (node (ref "C2") (pin "1") (pinfunction "1_1") (pintype "passive"))
      (node (ref "U1") (pin "A23") (pinfunction "XC2_A23") (pintype "output"))
      (node (ref "X1") (pin "3") (pinfunction "OUT_3") (pintype "passive"))
    )
    (net (code "44") (name "GND") (class "Default")
      (node (ref "C11") (pin "2") (pinfunction "2_2") (pintype "passive"))
      (node (ref "C12") (pin "2") (pinfunction "2_2") (pintype "passive"))
      (node (ref "C13") (pin "2") (pinfunction "2_2") (pintype "passive"))
      (node (ref "C14") (pin "2") (pinfunction "2_2") (pintype "passive"))
      (node (ref "C15") (pin "1") (pinfunction "1_1") (pintype "passive"))
      (node (ref "C16") (pin "2") (pinfunction "2_2") (pintype "passive"))
      (node (ref "C17") (pin "2") (pinfunction "2_2") (pintype "passive"))
      (node (ref "C18") (pin "2") (pinfunction "2_2") (pintype "passive"))
      (node (ref "C19") (pin "2") (pinfunction "2_2") (pintype "passive"))
      (node (ref "C2") (pin "2") (pinfunction "2_2") (pintype "passive"))
      (node (ref "C20") (pin "2") (pinfunction "2_2") (pintype "passive"))
      (node (ref "C21") (pin "1") (pinfunction "1_1") (pintype "passive"))
      (node (ref "C22") (pin "1") (pinfunction "1_1") (pintype "passive"))
      (node (ref "C23") (pin "1") (pinfunction "1_1") (pintype "passive"))
      (node (ref "C24") (pin "1") (pinfunction "1_1") (pintype "passive"))
      (node (ref "C25") (pin "2") (pinfunction "2_2") (pintype "passive"))
      (node (ref "C26") (pin "1") (pinfunction "1_1") (pintype "passive"))
      (node (ref "C27") (pin "1") (pinfunction "1_1") (pintype "passive"))
      (node (ref "C28") (pin "1") (pinfunction "1_1") (pintype "passive"))
      (node (ref "C29") (pin "2") (pinfunction "2_2") (pintype "passive"))
      (node (ref "C3") (pin "1") (pinfunction "1_1") (pintype "passive"))
      (node (ref "C4") (pin "1") (pinfunction "1_1") (pintype "passive"))
      (node (ref "C5") (pin "2") (pinfunction "2_2") (pintype "passive"))
      (node (ref "C6") (pin "2") (pinfunction "2_2") (pintype "passive"))
      (node (ref "C7") (pin "2") (pinfunction "2_2") (pintype "passive"))
      (node (ref "C8") (pin "2") (pinfunction "2_2") (pintype "passive"))
      (node (ref "C9") (pin "2") (pinfunction "2_2") (pintype "passive"))
      (node (ref "D1") (pin "1") (pinfunction "GND_1") (pintype "passive"))
      (node (ref "FB2") (pin "2") (pinfunction "2_2") (pintype "passive"))
      (node (ref "GND1") (pin "1") (pinfunction "1_1") (pintype "passive"))
      (node (ref "GND2") (pin "1") (pinfunction "1_1") (pintype "passive"))
      (node (ref "GND3") (pin "1") (pinfunction "1_1") (pintype "passive"))
      (node (ref "GND4") (pin "1") (pinfunction "1_1") (pintype "passive"))
      (node (ref "J2") (pin "3") (pinfunction "3_3") (pintype "passive"))
      (node (ref "P1") (pin "3") (pinfunction "3_3") (pintype "passive"))
      (node (ref "P1") (pin "5") (pinfunction "5_5") (pintype "passive"))
      (node (ref "P1") (pin "9") (pinfunction "9_9") (pintype "passive"))
      (node (ref "SW1") (pin "2") (pinfunction "COM_2") (pintype "passive"))
      (node (ref "SW2") (pin "2") (pinfunction "COM_2") (pintype "passive"))
      (node (ref "U1") (pin "74") (pinfunction "GND_74") (pintype "power_in"))
      (node (ref "U1") (pin "B15") (pinfunction "P1.14_B15") (pintype "bidirectional"))
      (node (ref "U1") (pin "B7") (pinfunction "VSS_B7") (pintype "power_in"))
      (node (ref "U1") (pin "F23") (pinfunction "VSS_PA_F23") (pintype "power_in"))
      (node (ref "X1") (pin "2") (pinfunction "GND_2") (pintype "passive"))
    )
    (net (code "45") (name "Net-(C1-Pad2)") (class "Default")
      (node (ref "C1") (pin "2") (pinfunction "2_2") (pintype "passive"))
      (node (ref "X1") (pin "4") (pinfunction "GND_4") (pintype "passive"))
    )
    (net (code "46") (name "Net-(J1-D+)") (class "Default")
      (node (ref "D+") (pin "1") (pinfunction "1_1") (pintype "passive"))
      (node (ref "J1") (pin "3") (pinfunction "D+_3") (pintype "passive"))
      (node (ref "SB4") (pin "2") (pinfunction "1_2") (pintype "passive"))
    )
    (net (code "47") (name "Net-(J1-D-)") (class "Default")
      (node (ref "D-") (pin "1") (pinfunction "1_1") (pintype "passive"))
      (node (ref "J1") (pin "2") (pinfunction "D-_2") (pintype "passive"))
      (node (ref "SB3") (pin "2") (pinfunction "1_2") (pintype "passive"))
    )
    (net (code "48") (name "Net-(J1-GND)") (class "Default")
      (node (ref "FB2") (pin "1") (pinfunction "1_1") (pintype "passive"))
      (node (ref "J1") (pin "4") (pinfunction "GND_4") (pintype "passive"))
      (node (ref "UGND") (pin "1") (pinfunction "1_1") (pintype "passive"))
    )
    (net (code "49") (name "Net-(L2-Pad1)") (class "Default")
      (node (ref "L2") (pin "1") (pinfunction "1_1") (pintype "passive"))
      (node (ref "L3") (pin "2") (pinfunction "2_2") (pintype "passive"))
    )
    (net (code "50") (name "Net-(LD1-C)") (class "Default")
      (node (ref "LD1") (pin "1") (pinfunction "C_1") (pintype "passive"))
      (node (ref "R3") (pin "2") (pinfunction "2_2") (pintype "passive"))
    )
    (net (code "51") (name "Net-(LD2-C_BLUE)") (class "Default")
      (node (ref "LD2") (pin "3") (pinfunction "C_BLUE_3") (pintype "passive"))
      (node (ref "R6") (pin "2") (pinfunction "2_2") (pintype "passive"))
    )
    (net (code "52") (name "Net-(LD2-C_GREEN)") (class "Default")
      (node (ref "LD2") (pin "2") (pinfunction "C_GREEN_2") (pintype "passive"))
      (node (ref "R5") (pin "2") (pinfunction "2_2") (pintype "passive"))
    )
    (net (code "53") (name "Net-(LD2-C_RED)") (class "Default")
      (node (ref "LD2") (pin "1") (pinfunction "C_RED_1") (pintype "passive"))
      (node (ref "R4") (pin "2") (pinfunction "2_2") (pintype "passive"))
    )
    (net (code "54") (name "Net-(SB1-1)") (class "Default")
      (node (ref "SB1") (pin "2") (pinfunction "1_2") (pintype "passive"))
      (node (ref "SB2") (pin "1") (pinfunction "0_1") (pintype "passive"))
      (node (ref "U1") (pin "Y2") (pinfunction "VDDH_Y2") (pintype "power_in"))
    )
    (net (code "55") (name "Net-(U1-ANT)") (class "Default")
      (node (ref "C3") (pin "2") (pinfunction "2_2") (pintype "passive"))
      (node (ref "L1") (pin "1") (pinfunction "1_1") (pintype "passive"))
      (node (ref "U1") (pin "H23") (pinfunction "ANT_H23") (pintype "bidirectional"))
    )
    (net (code "56") (name "Net-(U1-DCC)") (class "Default")
      (node (ref "L2") (pin "2") (pinfunction "2_2") (pintype "passive"))
      (node (ref "U1") (pin "B3") (pinfunction "DCC_B3") (pintype "output"))
    )
    (net (code "57") (name "Net-(U1-DCCH)") (class "Default")
      (node (ref "L4") (pin "2") (pinfunction "2_2") (pintype "passive"))
      (node (ref "U1") (pin "AB2") (pinfunction "DCCH_AB2") (pintype "power_in"))
    )
    (net (code "58") (name "Net-(U1-DEC2)") (class "Default")
      (node (ref "C13") (pin "1") (pinfunction "1_1") (pintype "passive"))
      (node (ref "U1") (pin "A18") (pinfunction "DEC2_A18") (pintype "power_in"))
    )
    (net (code "59") (name "Net-(U1-DEC5)") (class "Default")
      (node (ref "C9") (pin "1") (pinfunction "1_1") (pintype "passive"))
      (node (ref "U1") (pin "N24") (pinfunction "DEC5_N24") (pintype "power_in"))
    )
    (net (code "60") (name "Net-(U1-DECUSB)") (class "Default")
      (node (ref "C20") (pin "1") (pinfunction "1_1") (pintype "passive"))
      (node (ref "U1") (pin "AC5") (pinfunction "DECUSB_AC5") (pintype "power_in"))
    )
    (net (code "61") (name "VBUS") (class "Default")
      (node (ref "C22") (pin "2") (pinfunction "2_2") (pintype "passive"))
      (node (ref "FB1") (pin "2") (pinfunction "2_2") (pintype "passive"))
      (node (ref "R7") (pin "2") (pinfunction "2_2") (pintype "passive"))
    )
    (net (code "62") (name "VBUS'") (class "Default")
      (node (ref "C21") (pin "2") (pinfunction "2_2") (pintype "passive"))
      (node (ref "C23") (pin "2") (pinfunction "2_2") (pintype "passive"))
      (node (ref "C24") (pin "2") (pinfunction "2_2") (pintype "passive"))
      (node (ref "D1") (pin "4") (pinfunction "VCC_4") (pintype "passive"))
      (node (ref "FB1") (pin "1") (pinfunction "1_1") (pintype "passive"))
      (node (ref "J1") (pin "1") (pinfunction "VBUS_1") (pintype "passive"))
      (node (ref "J2") (pin "5") (pinfunction "5_5") (pintype "passive"))
      (node (ref "VBUS1") (pin "1") (pinfunction "1_1") (pintype "passive"))
      (node (ref "VBUS2") (pin "1") (pinfunction "1_1") (pintype "passive"))
    )
    (net (code "63") (name "VBUS_nRF") (class "Default")
      (node (ref "C19") (pin "1") (pinfunction "1_1") (pintype "passive"))
      (node (ref "R7") (pin "1") (pinfunction "1_1") (pintype "passive"))
      (node (ref "SB2") (pin "2") (pinfunction "1_2") (pintype "passive"))
      (node (ref "U1") (pin "AD2") (pinfunction "VBUS_AD2") (pintype "power_in"))
    )
    (net (code "64") (name "VDD_nRF") (class "Default")
      (node (ref "C12") (pin "1") (pinfunction "1_1") (pintype "passive"))
      (node (ref "C14") (pin "1") (pinfunction "1_1") (pintype "passive"))
      (node (ref "C6") (pin "1") (pinfunction "1_1") (pintype "passive"))
      (node (ref "C7") (pin "1") (pinfunction "1_1") (pintype "passive"))
      (node (ref "C8") (pin "1") (pinfunction "1_1") (pintype "passive"))
      (node (ref "J2") (pin "1") (pinfunction "1_1") (pintype "passive"))
      (node (ref "L4") (pin "1") (pinfunction "1_1") (pintype "passive"))
      (node (ref "LD1") (pin "2") (pinfunction "A_2") (pintype "passive"))
      (node (ref "LD2") (pin "4") (pinfunction "A_4") (pintype "passive"))
      (node (ref "P1") (pin "1") (pinfunction "1_1") (pintype "passive"))
      (node (ref "R2") (pin "2") (pinfunction "2_2") (pintype "passive"))
      (node (ref "SB1") (pin "1") (pinfunction "0_1") (pintype "passive"))
      (node (ref "U1") (pin "A22") (pinfunction "VDD_A22") (pintype "power_in"))
      (node (ref "U1") (pin "AD14") (pinfunction "VDD_AD14") (pintype "power_in"))
      (node (ref "U1") (pin "AD23") (pinfunction "VDD_AD23") (pintype "power_in"))
      (node (ref "U1") (pin "B1") (pinfunction "VDD_B1") (pintype "power_in"))
      (node (ref "U1") (pin "W1") (pinfunction "VDD_W1") (pintype "power_in"))
      (node (ref "VDD OUT") (pin "1") (pinfunction "1_1") (pintype "passive"))
      (node (ref "VDD nRF") (pin "1") (pinfunction "1_1") (pintype "passive"))
    )
    (net (code "65") (name "unconnected-(J2-Pad6)") (class "Default")
      (node (ref "J2") (pin "6") (pinfunction "6_6") (pintype "passive"))
    )
    (net (code "66") (name "unconnected-(J2-Pad7)") (class "Default")
      (node (ref "J2") (pin "7") (pinfunction "7_7") (pintype "passive"))
    )
    (net (code "67") (name "unconnected-(J2-Pad8)") (class "Default")
      (node (ref "J2") (pin "8") (pinfunction "8_8") (pintype "passive"))
    )
    (net (code "68") (name "unconnected-(J2-Pad9)") (class "Default")
      (node (ref "J2") (pin "9") (pinfunction "9_9") (pintype "passive"))
    )
    (net (code "69") (name "unconnected-(J2-Pad10)") (class "Default")
      (node (ref "J2") (pin "10") (pinfunction "10_10") (pintype "passive"))
    )
    (net (code "70") (name "unconnected-(P1-Pad6)") (class "Default")
      (node (ref "P1") (pin "6") (pinfunction "6_6") (pintype "passive"))
    )
    (net (code "71") (name "unconnected-(P1-Pad7)") (class "Default")
      (node (ref "P1") (pin "7") (pinfunction "7_7") (pintype "passive"))
    )
    (net (code "72") (name "unconnected-(P1-Pad8)") (class "Default")
      (node (ref "P1") (pin "8") (pinfunction "8_8") (pintype "passive"))
    )
    (net (code "73") (name "unconnected-(U1-P0.03{slash}AIN1-PadB13)") (class "Default")
      (node (ref "U1") (pin "B13") (pinfunction "P0.03/AIN1_B13") (pintype "bidirectional"))
    )
    (net (code "74") (name "unconnected-(U1-P0.05{slash}AIN3-PadK2)") (class "Default")
      (node (ref "U1") (pin "K2") (pinfunction "P0.05/AIN3_K2") (pintype "bidirectional"))
    )
    (net (code "75") (name "unconnected-(U1-P0.07-PadM2)") (class "Default")
      (node (ref "U1") (pin "M2") (pinfunction "P0.07_M2") (pintype "bidirectional"))
    )
    (net (code "76") (name "unconnected-(U1-P0.16-PadAC11)") (class "Default")
      (node (ref "U1") (pin "AC11") (pinfunction "P0.16_AC11") (pintype "bidirectional"))
    )
    (net (code "77") (name "unconnected-(U1-P0.27-PadH2)") (class "Default")
      (node (ref "U1") (pin "H2") (pinfunction "P0.27_H2") (pintype "bidirectional"))
    )
    (net (code "78") (name "unconnected-(U1-P0.28{slash}AIN4-PadB11)") (class "Default")
      (node (ref "U1") (pin "B11") (pinfunction "P0.28/AIN4_B11") (pintype "bidirectional"))
    )
    (net (code "79") (name "unconnected-(U1-P0.30{slash}AIN6-PadB9)") (class "Default")
      (node (ref "U1") (pin "B9") (pinfunction "P0.30/AIN6_B9") (pintype "bidirectional"))
    )
    (net (code "80") (name "unconnected-(U1-P1.03-PadV23)") (class "Default")
      (node (ref "U1") (pin "V23") (pinfunction "P1.03_V23") (pintype "bidirectional"))
    )
    (net (code "81") (name "unconnected-(U1-P1.05-PadT23)") (class "Default")
      (node (ref "U1") (pin "T23") (pinfunction "P1.05_T23") (pintype "bidirectional"))
    )
    (net (code "82") (name "unconnected-(U1-P1.08-PadP2)") (class "Default")
      (node (ref "U1") (pin "P2") (pinfunction "P1.08_P2") (pintype "bidirectional"))
    )
    (net (code "83") (name "unconnected-(U1-P1.12-PadB17)") (class "Default")
      (node (ref "U1") (pin "B17") (pinfunction "P1.12_B17") (pintype "bidirectional"))
    )
  )
)
